# PWR_5to3_3_AMS1117.net
KiCad netlist of a schematic drawn in Altium Designer
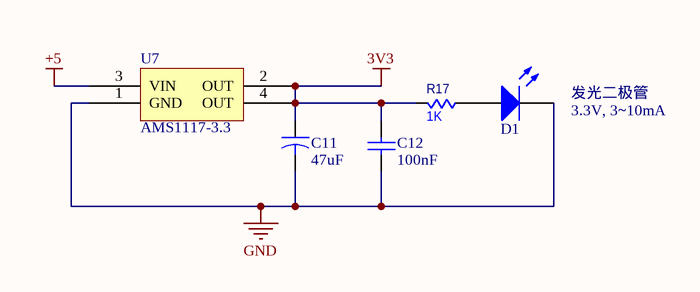
[diagram p0: PWR_5to3.3_AMS1117.SchDoc]

(export (version "E")
  (design (tool "Eeschema 10.0.6"))
  (components
    (comp (ref "C11")
      (value "47uF")
      (footprint "Cap-47uF")
      (description "Capacitor")
      (fields (field (name "Comment") "Cap Pol") (field (name "PUBLISHER") "Altium Limited"))
      (libsource (lib "haoze") (part "Cap Pol"))
    )
    (comp (ref "C12")
      (value "100nF")
      (footprint "0603")
      (description "无极性电容")
      (fields (field (name "Comment") "Cap") (field (name "PUBLISHER") "Altium Limited"))
      (libsource (lib "haoze") (part "Cap"))
    )
    (comp (ref "D1")
      (value "LED")
      (footprint "LED_0805")
      (description "发光二极管")
      (fields (field (name "PUBLISHER") "Altium Limited"))
      (libsource (lib "SMT") (part "LED"))
    )
    (comp (ref "R17")
      (value "1K")
      (footprint "0603")
      (description "常规电阻")
      (fields (field (name "Comment") "Res"))
      (libsource (lib "haoze") (part "Res"))
    )
    (comp (ref "U7")
      (value "AMS1117-3.3")
      (footprint "SOT223")
      (description "DCDC")
      (libsource (lib "haoze") (part "AMS1117-3.3"))
    )
  )
  (nets
    (net (code "1") (name "+5") (class "Default")
      (node (ref "U7") (pin "3") (pinfunction "VIN_3") (pintype "passive"))
    )
    (net (code "2") (name "3V3") (class "Default")
      (node (ref "C11") (pin "1") (pinfunction "1_1") (pintype "passive"))
      (node (ref "C12") (pin "2") (pinfunction "2_2") (pintype "passive"))
      (node (ref "R17") (pin "2") (pinfunction "2_2") (pintype "passive"))
      (node (ref "U7") (pin "2") (pinfunction "OUT_2") (pintype "passive"))
      (node (ref "U7") (pin "4") (pinfunction "OUT_4") (pintype "passive"))
    )
    (net (code "3") (name "GND") (class "Default")
      (node (ref "C11") (pin "2") (pinfunction "2_2") (pintype "passive"))
      (node (ref "C12") (pin "1") (pinfunction "1_1") (pintype "passive"))
      (node (ref "D1") (pin "2") (pinfunction "K_2") (pintype "passive"))
      (node (ref "U7") (pin "1") (pinfunction "GND_1") (pintype "passive"))
    )
    (net (code "4") (name "Net-(D1-A)") (class "Default")
      (node (ref "D1") (pin "1") (pinfunction "A_1") (pintype "passive"))
      (node (ref "R17") (pin "1") (pinfunction "1_1") (pintype "passive"))
    )
  )
)
